# Principal_V01_R00.net
KiCad netlist of a schematic drawn in Altium Designer
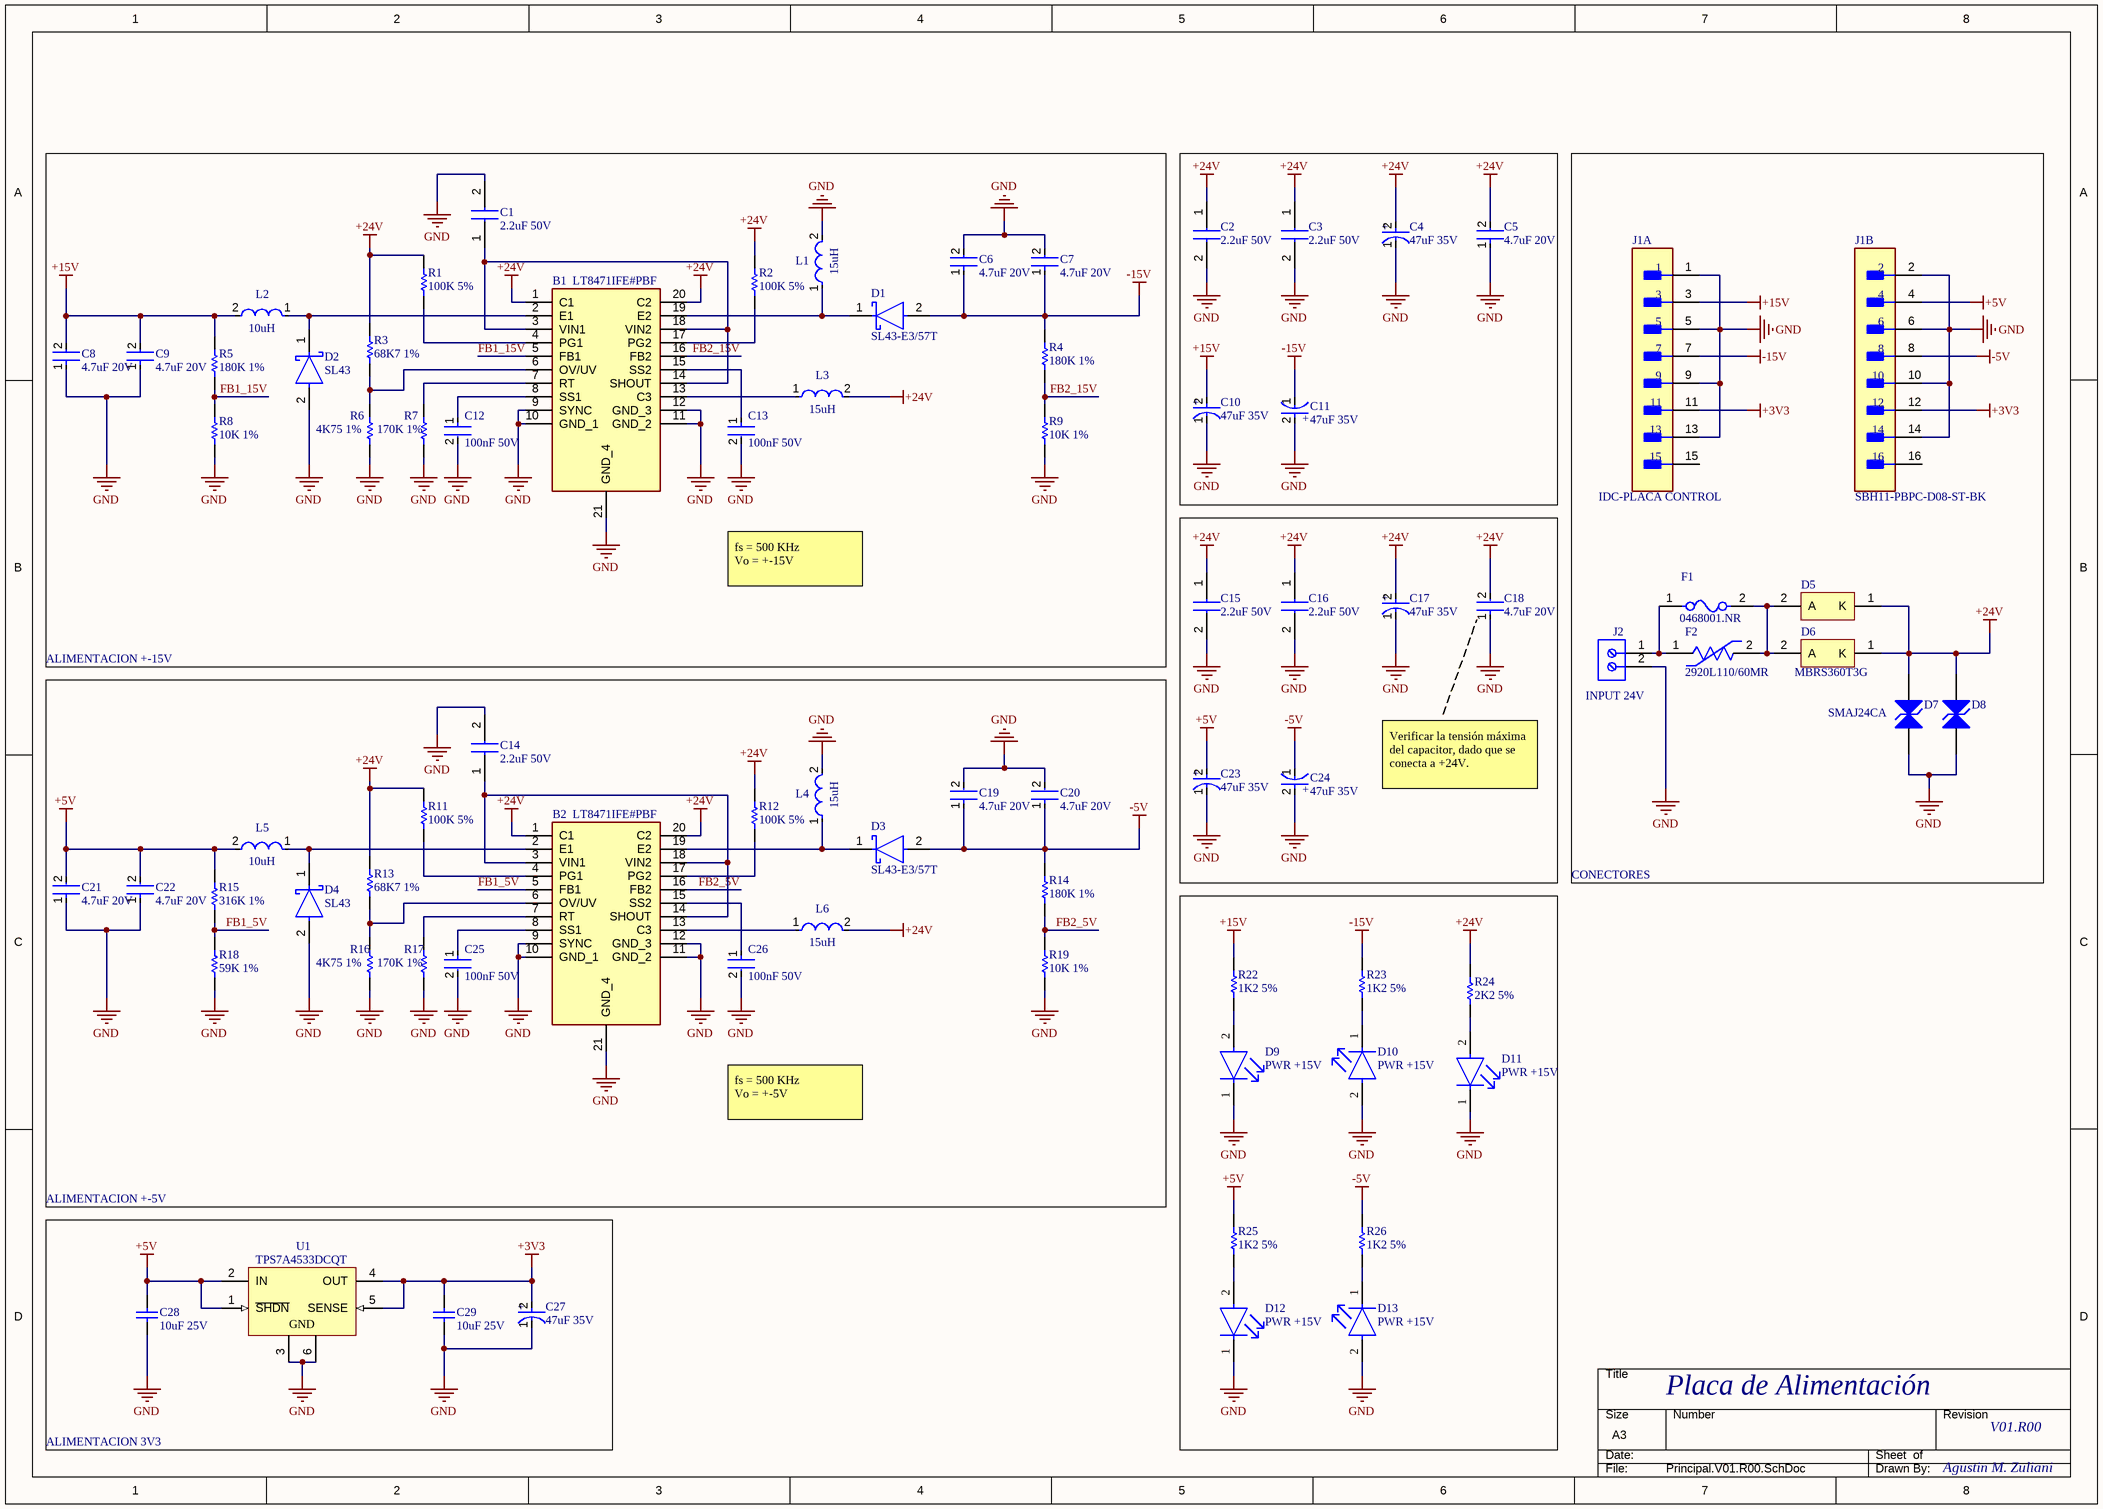
[diagram p0: Principal.V01.R00.SchDoc]

(export (version "E")
  (design (tool "Eeschema 10.0.6"))
  (components
    (comp (ref "B1")
      (value "LT8471IFE#PBF")
      (footprint "SOP65P640X120-21N")
      (fields (field (name "MOUSER PART NUMBER") "584-LT8471IFE#PBF"))
      (libsource (lib "LT8471IFE#PBF") (part "LT8471IFE#PBF"))
    )
    (comp (ref "B2")
      (value "LT8471IFE#PBF")
      (footprint "SOP65P640X120-21N")
      (fields (field (name "MOUSER PART NUMBER") "584-LT8471IFE#PBF"))
      (libsource (lib "LT8471IFE#PBF") (part "LT8471IFE#PBF"))
    )
    (comp (ref "C1")
      (value "2.2uF 50V")
      (footprint "SamacSys:MBASx31x")
      (description "Capacitor")
      (fields (field (name "MANUFACTURER_PART_NUMBER") "MBASU31LSB7225KTNA01"))
      (libsource (lib "SamacSys") (part "MBASU31LSB7225KTNA01"))
    )
    (comp (ref "C2")
      (value "2.2uF 50V")
      (footprint "SamacSys:MBASx31x")
      (description "Capacitor")
      (fields (field (name "MANUFACTURER_PART_NUMBER") "MBASU31LSB7225KTNA01"))
      (libsource (lib "SamacSys") (part "MBASU31LSB7225KTNA01"))
    )
    (comp (ref "C3")
      (value "2.2uF 50V")
      (footprint "SamacSys:MBASx31x")
      (description "Capacitor")
      (fields (field (name "MANUFACTURER_PART_NUMBER") "MBASU31LSB7225KTNA01"))
      (libsource (lib "SamacSys") (part "MBASU31LSB7225KTNA01"))
    )
    (comp (ref "C4")
      (value "47uF 35V")
      (footprint "FP-FK-D-MFG")
      (description "CAP ALUM 47UF 20% 35V SMD")
      (fields
        (field (name "MANUFACTURER") "Panasonic")
        (field (name "OCTOPART") "https://octopart.com/eeefk1v470p-panasonic-4642848")
      )
      (libsource (lib "Altium Content Vault") (part "a00bbbee19879c290e62620ae7e47b1"))
    )
    (comp (ref "C5")
      (value "4.7uF 20V")
      (footprint "FP-CC1206-1_25-MFG")
      (description "CAP CER 1UF 10V X7R 1206")
      (fields
        (field (name "MANUFACTURER") "Yageo")
        (field (name "OCTOPART") "https://octopart.com/cc1206kkx7r6bb105-yageo-21769912")
      )
      (libsource (lib "Altium Content Vault") (part "11868f565c42a9108669ba33697ecf6"))
    )
    (comp (ref "C6")
      (value "4.7uF 20V")
      (footprint "FP-CC1206-1_25-MFG")
      (description "CAP CER 1UF 10V X7R 1206")
      (fields
        (field (name "MANUFACTURER") "Yageo")
        (field (name "OCTOPART") "https://octopart.com/cc1206kkx7r6bb105-yageo-21769912")
      )
      (libsource (lib "Altium Content Vault") (part "11868f565c42a9108669ba33697ecf6"))
    )
    (comp (ref "C7")
      (value "4.7uF 20V")
      (footprint "FP-CC1206-1_25-MFG")
      (description "CAP CER 1UF 10V X7R 1206")
      (fields
        (field (name "MANUFACTURER") "Yageo")
        (field (name "OCTOPART") "https://octopart.com/cc1206kkx7r6bb105-yageo-21769912")
      )
      (libsource (lib "Altium Content Vault") (part "11868f565c42a9108669ba33697ecf6"))
    )
    (comp (ref "C8")
      (value "4.7uF 20V")
      (footprint "FP-CC1206-1_25-MFG")
      (description "CAP CER 1UF 10V X7R 1206")
      (fields
        (field (name "MANUFACTURER") "Yageo")
        (field (name "OCTOPART") "https://octopart.com/cc1206kkx7r6bb105-yageo-21769912")
      )
      (libsource (lib "Altium Content Vault") (part "11868f565c42a9108669ba33697ecf6"))
    )
    (comp (ref "C9")
      (value "4.7uF 20V")
      (footprint "FP-CC1206-1_25-MFG")
      (description "CAP CER 1UF 10V X7R 1206")
      (fields
        (field (name "MANUFACTURER") "Yageo")
        (field (name "OCTOPART") "https://octopart.com/cc1206kkx7r6bb105-yageo-21769912")
      )
      (libsource (lib "Altium Content Vault") (part "11868f565c42a9108669ba33697ecf6"))
    )
    (comp (ref "C10")
      (value "47uF 35V")
      (footprint "FP-FK-D-MFG")
      (description "CAP ALUM 47UF 20% 35V SMD")
      (fields
        (field (name "MANUFACTURER") "Panasonic")
        (field (name "OCTOPART") "https://octopart.com/eeefk1v470p-panasonic-4642848")
      )
      (libsource (lib "Altium Content Vault") (part "a00bbbee19879c290e62620ae7e47b1"))
    )
    (comp (ref "C11")
      (value "47uF 35V")
      (footprint "FP-FK-D-MFG")
      (description "CAP ALUM 47UF 20% 35V SMD")
      (fields
        (field (name "MANUFACTURER") "Panasonic")
        (field (name "OCTOPART") "https://octopart.com/eeefk1v470p-panasonic-4642848")
      )
      (libsource (lib "Altium Content Vault") (part "a00bbbee19879c290e62620ae7e47b1"))
    )
    (comp (ref "C12")
      (value "100nF 50V")
      (footprint "FP-C1206C-EB-MFG")
      (description "CAP CER 0.1UF 50V X7R 1206")
      (fields
        (field (name "MANUFACTURER") "KEMET")
        (field (name "OCTOPART") "https://octopart.com/c1206c104k5racauto-kemet-12595586")
      )
      (libsource (lib "Altium Content Vault") (part "b4654b650e69147ec39a6b967a45e02"))
    )
    (comp (ref "C13")
      (value "100nF 50V")
      (footprint "FP-C1206C-EB-MFG")
      (description "CAP CER 0.1UF 50V X7R 1206")
      (fields
        (field (name "MANUFACTURER") "KEMET")
        (field (name "OCTOPART") "https://octopart.com/c1206c104k5racauto-kemet-12595586")
      )
      (libsource (lib "Altium Content Vault") (part "b4654b650e69147ec39a6b967a45e02"))
    )
    (comp (ref "C14")
      (value "2.2uF 50V")
      (footprint "SamacSys:MBASx31x")
      (description "Capacitor")
      (fields (field (name "MANUFACTURER_PART_NUMBER") "MBASU31LSB7225KTNA01"))
      (libsource (lib "SamacSys") (part "MBASU31LSB7225KTNA01"))
    )
    (comp (ref "C15")
      (value "2.2uF 50V")
      (footprint "SamacSys:MBASx31x")
      (description "Capacitor")
      (fields (field (name "MANUFACTURER_PART_NUMBER") "MBASU31LSB7225KTNA01"))
      (libsource (lib "SamacSys") (part "MBASU31LSB7225KTNA01"))
    )
    (comp (ref "C16")
      (value "2.2uF 50V")
      (footprint "SamacSys:MBASx31x")
      (description "Capacitor")
      (fields (field (name "MANUFACTURER_PART_NUMBER") "MBASU31LSB7225KTNA01"))
      (libsource (lib "SamacSys") (part "MBASU31LSB7225KTNA01"))
    )
    (comp (ref "C17")
      (value "47uF 35V")
      (footprint "FP-FK-D-MFG")
      (description "CAP ALUM 47UF 20% 35V SMD")
      (fields
        (field (name "MANUFACTURER") "Panasonic")
        (field (name "OCTOPART") "https://octopart.com/eeefk1v470p-panasonic-4642848")
      )
      (libsource (lib "Altium Content Vault") (part "a00bbbee19879c290e62620ae7e47b1"))
    )
    (comp (ref "C18")
      (value "4.7uF 20V")
      (footprint "FP-CC1206-1_25-MFG")
      (description "CAP CER 1UF 10V X7R 1206")
      (fields
        (field (name "MANUFACTURER") "Yageo")
        (field (name "OCTOPART") "https://octopart.com/cc1206kkx7r6bb105-yageo-21769912")
      )
      (libsource (lib "Altium Content Vault") (part "11868f565c42a9108669ba33697ecf6"))
    )
    (comp (ref "C19")
      (value "4.7uF 20V")
      (footprint "FP-CC1206-1_25-MFG")
      (description "CAP CER 1UF 10V X7R 1206")
      (fields
        (field (name "MANUFACTURER") "Yageo")
        (field (name "OCTOPART") "https://octopart.com/cc1206kkx7r6bb105-yageo-21769912")
      )
      (libsource (lib "Altium Content Vault") (part "11868f565c42a9108669ba33697ecf6"))
    )
    (comp (ref "C20")
      (value "4.7uF 20V")
      (footprint "FP-CC1206-1_25-MFG")
      (description "CAP CER 1UF 10V X7R 1206")
      (fields
        (field (name "MANUFACTURER") "Yageo")
        (field (name "OCTOPART") "https://octopart.com/cc1206kkx7r6bb105-yageo-21769912")
      )
      (libsource (lib "Altium Content Vault") (part "11868f565c42a9108669ba33697ecf6"))
    )
    (comp (ref "C21")
      (value "4.7uF 20V")
      (footprint "FP-CC1206-1_25-MFG")
      (description "CAP CER 1UF 10V X7R 1206")
      (fields
        (field (name "MANUFACTURER") "Yageo")
        (field (name "OCTOPART") "https://octopart.com/cc1206kkx7r6bb105-yageo-21769912")
      )
      (libsource (lib "Altium Content Vault") (part "11868f565c42a9108669ba33697ecf6"))
    )
    (comp (ref "C22")
      (value "4.7uF 20V")
      (footprint "FP-CC1206-1_25-MFG")
      (description "CAP CER 1UF 10V X7R 1206")
      (fields
        (field (name "MANUFACTURER") "Yageo")
        (field (name "OCTOPART") "https://octopart.com/cc1206kkx7r6bb105-yageo-21769912")
      )
      (libsource (lib "Altium Content Vault") (part "11868f565c42a9108669ba33697ecf6"))
    )
    (comp (ref "C23")
      (value "47uF 35V")
      (footprint "FP-FK-D-MFG")
      (description "CAP ALUM 47UF 20% 35V SMD")
      (fields
        (field (name "MANUFACTURER") "Panasonic")
        (field (name "OCTOPART") "https://octopart.com/eeefk1v470p-panasonic-4642848")
      )
      (libsource (lib "Altium Content Vault") (part "a00bbbee19879c290e62620ae7e47b1"))
    )
    (comp (ref "C24")
      (value "47uF 35V")
      (footprint "FP-FK-D-MFG")
      (description "CAP ALUM 47UF 20% 35V SMD")
      (fields
        (field (name "MANUFACTURER") "Panasonic")
        (field (name "OCTOPART") "https://octopart.com/eeefk1v470p-panasonic-4642848")
      )
      (libsource (lib "Altium Content Vault") (part "a00bbbee19879c290e62620ae7e47b1"))
    )
    (comp (ref "C25")
      (value "100nF 50V")
      (footprint "FP-C1206C-EB-MFG")
      (description "CAP CER 0.1UF 50V X7R 1206")
      (fields
        (field (name "MANUFACTURER") "KEMET")
        (field (name "OCTOPART") "https://octopart.com/c1206c104k5racauto-kemet-12595586")
      )
      (libsource (lib "Altium Content Vault") (part "b4654b650e69147ec39a6b967a45e02"))
    )
    (comp (ref "C26")
      (value "100nF 50V")
      (footprint "FP-C1206C-EB-MFG")
      (description "CAP CER 0.1UF 50V X7R 1206")
      (fields
        (field (name "MANUFACTURER") "KEMET")
        (field (name "OCTOPART") "https://octopart.com/c1206c104k5racauto-kemet-12595586")
      )
      (libsource (lib "Altium Content Vault") (part "b4654b650e69147ec39a6b967a45e02"))
    )
    (comp (ref "C27")
      (value "47uF 35V")
      (footprint "FP-FK-D-MFG")
      (description "CAP ALUM 47UF 20% 35V SMD")
      (fields
        (field (name "MANUFACTURER") "Panasonic")
        (field (name "OCTOPART") "https://octopart.com/eeefk1v470p-panasonic-4642848")
      )
      (libsource (lib "Altium Content Vault") (part "a00bbbee19879c290e62620ae7e47b1"))
    )
    (comp (ref "C28")
      (value "10uF 25V")
      (footprint "CAPC1812(4532)280_L")
      (description "CAP 10uF 25V ±20% 1812 (4532 Metric) Thickness 2.8mm SMD")
      (fields (field (name "TOLERANCE") "Â±20%"))
      (libsource (lib "Altium Content Vault") (part "CAP"))
    )
    (comp (ref "C29")
      (value "10uF 25V")
      (footprint "CAPC1812(4532)280_L")
      (description "CAP 10uF 25V ±20% 1812 (4532 Metric) Thickness 2.8mm SMD")
      (fields (field (name "TOLERANCE") "Â±20%"))
      (libsource (lib "Altium Content Vault") (part "CAP"))
    )
    (comp (ref "D1")
      (value "SL43-E3/57T")
      (footprint "FP-95402-MFG")
      (description "DIODE SCHOTTKY 30V 4A DO214AB")
      (libsource (lib "Altium Content Vault") (part "1d6ec82d83fb6aee721767c19dac4b9"))
    )
    (comp (ref "D2")
      (value "SL43")
      (footprint "FP-95402-MFG")
      (description "DIODE SCHOTTKY 30V 4A DO214AB")
      (libsource (lib "Altium Content Vault") (part "1d6ec82d83fb6aee721767c19dac4b9"))
    )
    (comp (ref "D3")
      (value "SL43-E3/57T")
      (footprint "FP-95402-MFG")
      (description "DIODE SCHOTTKY 30V 4A DO214AB")
      (libsource (lib "Altium Content Vault") (part "1d6ec82d83fb6aee721767c19dac4b9"))
    )
    (comp (ref "D4")
      (value "SL43")
      (footprint "FP-95402-MFG")
      (description "DIODE SCHOTTKY 30V 4A DO214AB")
      (libsource (lib "Altium Content Vault") (part "1d6ec82d83fb6aee721767c19dac4b9"))
    )
    (comp (ref "D5")
      (value "MBRS360T3G")
      (footprint "ONSC-SMC-2-403-03_V")
      (description "Schottky Power Rectifier, 2-Pin SMC, Pb-Free, Tape and Reel")
      (fields (field (name "MANUFACTURER") "On Semiconductor"))
      (libsource (lib "Altium Content Vault") (part "ONSC-D-K1A2-2_A"))
    )
    (comp (ref "D6")
      (value "MBRS360T3G")
      (footprint "ONSC-SMC-2-403-03_V")
      (description "Schottky Power Rectifier, 2-Pin SMC, Pb-Free, Tape and Reel")
      (fields (field (name "MANUFACTURER") "On Semiconductor"))
      (libsource (lib "Altium Content Vault") (part "ONSC-D-K1A2-2_A"))
    )
    (comp (ref "D7")
      (value "SMAJ24CA")
      (footprint "VISH-DO-214AC-2_N")
      (fields
        (field (name "MANUFACTURER") "Vishay Semiconductor")
        (field (name "PARTNUMBER") "SMAJ24CA-E3/5A")
      )
      (libsource (lib "Altium Content Vault") (part "VISH-A1A2-2"))
    )
    (comp (ref "D8")
      (value "SMAJ24CA")
      (footprint "VISH-DO-214AC-2_N")
      (fields
        (field (name "MANUFACTURER") "Vishay Semiconductor")
        (field (name "PARTNUMBER") "SMAJ24CA-E3/5A")
      )
      (libsource (lib "Altium Content Vault") (part "VISH-A1A2-2"))
    )
    (comp (ref "D9")
      (value "PWR +15V")
      (footprint "FP-SML-LX0805UWC-TR-MFG")
      (description "SML-LX0805UWC-TR White LED, 0805 Diffused, Rectangle Lens SMD package")
      (libsource (lib "Altium Content Vault") (part "8706943c75ba83719d021d2fdc84c58"))
    )
    (comp (ref "D10")
      (value "PWR +15V")
      (footprint "FP-SML-LX0805UWC-TR-MFG")
      (description "SML-LX0805UWC-TR White LED, 0805 Diffused, Rectangle Lens SMD package")
      (libsource (lib "Altium Content Vault") (part "8706943c75ba83719d021d2fdc84c58"))
    )
    (comp (ref "D11")
      (value "PWR +15V")
      (footprint "FP-SML-LX0805UWC-TR-MFG")
      (description "SML-LX0805UWC-TR White LED, 0805 Diffused, Rectangle Lens SMD package")
      (libsource (lib "Altium Content Vault") (part "8706943c75ba83719d021d2fdc84c58"))
    )
    (comp (ref "D12")
      (value "PWR +15V")
      (footprint "FP-SML-LX0805UWC-TR-MFG")
      (description "SML-LX0805UWC-TR White LED, 0805 Diffused, Rectangle Lens SMD package")
      (libsource (lib "Altium Content Vault") (part "8706943c75ba83719d021d2fdc84c58"))
    )
    (comp (ref "D13")
      (value "PWR +15V")
      (footprint "FP-SML-LX0805UWC-TR-MFG")
      (description "SML-LX0805UWC-TR White LED, 0805 Diffused, Rectangle Lens SMD package")
      (libsource (lib "Altium Content Vault") (part "8706943c75ba83719d021d2fdc84c58"))
    )
    (comp (ref "F1")
      (value "0468001.NR")
      (footprint "FP-0468-MFG")
      (description "FUSE BOARD MNT 1A 63VAC/VDC 1206")
      (fields
        (field (name "MANUFACTURER") "Littelfuse")
        (field (name "OCTOPART") "https://octopart.com/0468001.nr-littelfuse-566477")
      )
      (libsource (lib "Altium Content Vault") (part "5bcf9b9f640e542cf0359d10258e979"))
    )
    (comp (ref "F2")
      (value "2920L110/60MR")
      (footprint "FP-2920L-MFG")
      (description "PTC RESET FUSE 60V 1.1A 2920")
      (fields
        (field (name "MANUFACTURER") "Littelfuse")
        (field (name "OCTOPART") "https://octopart.com/2920l110%2F60mr-littelfuse-75250824")
      )
      (libsource (lib "Altium Content Vault") (part "fc31388045fc42ab786d6d00b506e9f"))
    )
    (comp (ref "J1")
      (value "IDC-PLACA CONTROL")
      (footprint "FP-SBH11-PBPC-D08-ST-BK-MFG")
      (description "CONN HEADER VERT 16POS 2.54MM")
      (fields
        (field (name "OCTOPART") "https://octopart.com/sbh11-pbpc-d08-st-bk-sullins-12270491")
        (field (name "MANUFACTURER") "Sullins")
      )
      (libsource (lib "Altium Content Vault") (part "4b6d22b45e2f925f038cba5d936fbcc"))
    )
    (comp (ref "J2")
      (value "INPUT 24V")
      (footprint "691111710002")
      (description "111 Series 5MM Pitch Straight, Pcb Terminal Block, Through Hole, 2 Way")
      (libsource (lib "Altium Content Vault") (part "TBL - 1R - 02P - Screw"))
    )
    (comp (ref "L1")
      (value "15uH")
      (footprint "FP-NR6045-MFG")
      (description "Shielded Wirewound Inductor 15uH 20% 2.3A 91mΩ SMD")
      (fields (field (name "TOLERANCE") "20%"))
      (libsource (lib "") (part "725321dda6339637d4d059423bc1c3c_1"))
    )
    (comp (ref "L2")
      (value "10uH")
      (footprint "FP-NR10050-MFG")
      (description "Inductor Power Shielded Wirewound 10uH 20% 100KHz Ferrite 4.1A 32.5mΩ DCR T/R")
      (fields (field (name "TOLERANCE") "20%"))
      (libsource (lib "Altium Content Vault") (part "725321dda6339637d4d059423bc1c3c"))
    )
    (comp (ref "L3")
      (value "15uH")
      (footprint "FP-NR6045-MFG")
      (description "Shielded Wirewound Inductor 15uH 20% 2.3A 91mΩ SMD")
      (fields (field (name "TOLERANCE") "20%"))
      (libsource (lib "") (part "725321dda6339637d4d059423bc1c3c_1"))
    )
    (comp (ref "L4")
      (value "15uH")
      (footprint "FP-NR6045-MFG")
      (description "Shielded Wirewound Inductor 15uH 20% 2.3A 91mΩ SMD")
      (fields (field (name "TOLERANCE") "20%"))
      (libsource (lib "") (part "725321dda6339637d4d059423bc1c3c_1"))
    )
    (comp (ref "L5")
      (value "10uH")
      (footprint "FP-NR10050-MFG")
      (description "Inductor Power Shielded Wirewound 10uH 20% 100KHz Ferrite 4.1A 32.5mΩ DCR T/R")
      (fields (field (name "TOLERANCE") "20%"))
      (libsource (lib "Altium Content Vault") (part "725321dda6339637d4d059423bc1c3c"))
    )
    (comp (ref "L6")
      (value "15uH")
      (footprint "FP-NR6045-MFG")
      (description "Shielded Wirewound Inductor 15uH 20% 2.3A 91mΩ SMD")
      (fields (field (name "TOLERANCE") "20%"))
      (libsource (lib "") (part "725321dda6339637d4d059423bc1c3c_1"))
    )
    (comp (ref "R1")
      (value "100K 5%")
      (footprint "RESC0805(2012)_M")
      (description "124K 0.125W 1% 0805 (2012 Metric)  SMD")
      (fields (field (name "POWER") "0.125 W") (field (name "TOLERANCE") "1 %"))
      (libsource (lib "Altium Content Vault") (part "RES"))
    )
    (comp (ref "R2")
      (value "100K 5%")
      (footprint "RESC0805(2012)_M")
      (description "124K 0.125W 1% 0805 (2012 Metric)  SMD")
      (fields (field (name "POWER") "0.125 W") (field (name "TOLERANCE") "1 %"))
      (libsource (lib "Altium Content Vault") (part "RES"))
    )
    (comp (ref "R3")
      (value "68K7 1%")
      (footprint "RESC0805(2012)_M")
      (description "124K 0.125W 1% 0805 (2012 Metric)  SMD")
      (fields (field (name "POWER") "0.125 W") (field (name "TOLERANCE") "1 %"))
      (libsource (lib "Altium Content Vault") (part "RES"))
    )
    (comp (ref "R4")
      (value "180K 1%")
      (footprint "RESC0805(2012)_M")
      (description "124K 0.125W 1% 0805 (2012 Metric)  SMD")
      (fields (field (name "POWER") "0.125 W") (field (name "TOLERANCE") "1 %"))
      (libsource (lib "Altium Content Vault") (part "RES"))
    )
    (comp (ref "R5")
      (value "180K 1%")
      (footprint "RESC0805(2012)_M")
      (description "124K 0.125W 1% 0805 (2012 Metric)  SMD")
      (fields (field (name "POWER") "0.125 W") (field (name "TOLERANCE") "1 %"))
      (libsource (lib "Altium Content Vault") (part "RES"))
    )
    (comp (ref "R6")
      (value "4K75 1%")
      (footprint "RESC0805(2012)_M")
      (description "124K 0.125W 1% 0805 (2012 Metric)  SMD")
      (fields (field (name "POWER") "0.125 W") (field (name "TOLERANCE") "1 %"))
      (libsource (lib "Altium Content Vault") (part "RES"))
    )
    (comp (ref "R7")
      (value "170K 1%")
      (footprint "RESC0805(2012)_M")
      (description "124K 0.125W 1% 0805 (2012 Metric)  SMD")
      (fields (field (name "POWER") "0.125 W") (field (name "TOLERANCE") "1 %"))
      (libsource (lib "Altium Content Vault") (part "RES"))
    )
    (comp (ref "R8")
      (value "10K 1%")
      (footprint "RESC0805(2012)_M")
      (description "124K 0.125W 1% 0805 (2012 Metric)  SMD")
      (fields (field (name "POWER") "0.125 W") (field (name "TOLERANCE") "1 %"))
      (libsource (lib "Altium Content Vault") (part "RES"))
    )
    (comp (ref "R9")
      (value "10K 1%")
      (footprint "RESC0805(2012)_M")
      (description "124K 0.125W 1% 0805 (2012 Metric)  SMD")
      (fields (field (name "POWER") "0.125 W") (field (name "TOLERANCE") "1 %"))
      (libsource (lib "Altium Content Vault") (part "RES"))
    )
    (comp (ref "R11")
      (value "100K 5%")
      (footprint "RESC0805(2012)_M")
      (description "124K 0.125W 1% 0805 (2012 Metric)  SMD")
      (fields (field (name "POWER") "0.125 W") (field (name "TOLERANCE") "1 %"))
      (libsource (lib "Altium Content Vault") (part "RES"))
    )
    (comp (ref "R12")
      (value "100K 5%")
      (footprint "RESC0805(2012)_M")
      (description "124K 0.125W 1% 0805 (2012 Metric)  SMD")
      (fields (field (name "POWER") "0.125 W") (field (name "TOLERANCE") "1 %"))
      (libsource (lib "Altium Content Vault") (part "RES"))
    )
    (comp (ref "R13")
      (value "68K7 1%")
      (footprint "RESC0805(2012)_M")
      (description "124K 0.125W 1% 0805 (2012 Metric)  SMD")
      (fields (field (name "POWER") "0.125 W") (field (name "TOLERANCE") "1 %"))
      (libsource (lib "Altium Content Vault") (part "RES"))
    )
    (comp (ref "R14")
      (value "180K 1%")
      (footprint "RESC0805(2012)_M")
      (description "124K 0.125W 1% 0805 (2012 Metric)  SMD")
      (fields (field (name "POWER") "0.125 W") (field (name "TOLERANCE") "1 %"))
      (libsource (lib "Altium Content Vault") (part "RES"))
    )
    (comp (ref "R15")
      (value "316K 1%")
      (footprint "RESC0805(2012)_M")
      (description "124K 0.125W 1% 0805 (2012 Metric)  SMD")
      (fields (field (name "POWER") "0.125 W") (field (name "TOLERANCE") "1 %"))
      (libsource (lib "Altium Content Vault") (part "RES"))
    )
    (comp (ref "R16")
      (value "4K75 1%")
      (footprint "RESC0805(2012)_M")
      (description "124K 0.125W 1% 0805 (2012 Metric)  SMD")
      (fields (field (name "POWER") "0.125 W") (field (name "TOLERANCE") "1 %"))
      (libsource (lib "Altium Content Vault") (part "RES"))
    )
    (comp (ref "R17")
      (value "170K 1%")
      (footprint "RESC0805(2012)_M")
      (description "124K 0.125W 1% 0805 (2012 Metric)  SMD")
      (fields (field (name "POWER") "0.125 W") (field (name "TOLERANCE") "1 %"))
      (libsource (lib "Altium Content Vault") (part "RES"))
    )
    (comp (ref "R18")
      (value "59K 1%")
      (footprint "RESC0805(2012)_M")
      (description "124K 0.125W 1% 0805 (2012 Metric)  SMD")
      (fields (field (name "POWER") "0.125 W") (field (name "TOLERANCE") "1 %"))
      (libsource (lib "Altium Content Vault") (part "RES"))
    )
    (comp (ref "R19")
      (value "10K 1%")
      (footprint "RESC0805(2012)_M")
      (description "124K 0.125W 1% 0805 (2012 Metric)  SMD")
      (fields (field (name "POWER") "0.125 W") (field (name "TOLERANCE") "1 %"))
      (libsource (lib "Altium Content Vault") (part "RES"))
    )
    (comp (ref "R22")
      (value "1K2 5%")
      (footprint "RESC0805(2012)_M")
      (description "124K 0.125W 1% 0805 (2012 Metric)  SMD")
      (fields (field (name "POWER") "0.125 W") (field (name "TOLERANCE") "1 %"))
      (libsource (lib "Altium Content Vault") (part "RES"))
    )
    (comp (ref "R23")
      (value "1K2 5%")
      (footprint "RESC0805(2012)_M")
      (description "124K 0.125W 1% 0805 (2012 Metric)  SMD")
      (fields (field (name "POWER") "0.125 W") (field (name "TOLERANCE") "1 %"))
      (libsource (lib "Altium Content Vault") (part "RES"))
    )
    (comp (ref "R24")
      (value "2K2 5%")
      (footprint "RESC0805(2012)_M")
      (description "124K 0.125W 1% 0805 (2012 Metric)  SMD")
      (fields (field (name "POWER") "0.125 W") (field (name "TOLERANCE") "1 %"))
      (libsource (lib "Altium Content Vault") (part "RES"))
    )
    (comp (ref "R25")
      (value "1K2 5%")
      (footprint "RESC0805(2012)_M")
      (description "124K 0.125W 1% 0805 (2012 Metric)  SMD")
      (fields (field (name "POWER") "0.125 W") (field (name "TOLERANCE") "1 %"))
      (libsource (lib "Altium Content Vault") (part "RES"))
    )
    (comp (ref "R26")
      (value "1K2 5%")
      (footprint "RESC0805(2012)_M")
      (description "124K 0.125W 1% 0805 (2012 Metric)  SMD")
      (fields (field (name "POWER") "0.125 W") (field (name "TOLERANCE") "1 %"))
      (libsource (lib "Altium Content Vault") (part "RES"))
    )
    (comp (ref "U1")
      (value "TPS7A4533DCQT")
      (footprint "DCQ0006A_M")
      (fields (field (name "MANUFACTURER") "Texas Instruments"))
      (libsource (lib "Altium Content Vault") (part "TI-TXXXXAXXXDCQ_KTTX"))
    )
  )
  (nets
    (net (code "1") (name "+3V3") (class "Default")
      (node (ref "C27") (pin "2") (pinfunction "A_2") (pintype "passive"))
      (node (ref "C29") (pin "2") (pinfunction "2_2") (pintype "passive"))
      (node (ref "J1") (pin "11") (pinfunction "11_11") (pintype "passive"))
      (node (ref "J1") (pin "12") (pinfunction "12_12") (pintype "passive"))
      (node (ref "U1") (pin "4") (pinfunction "OUT_4") (pintype "power_in"))
      (node (ref "U1") (pin "5") (pinfunction "SENSE_5") (pintype "input"))
    )
    (net (code "2") (name "+5V") (class "Default")
      (node (ref "C21") (pin "2") (pinfunction "2_2") (pintype "passive"))
      (node (ref "C22") (pin "2") (pinfunction "2_2") (pintype "passive"))
      (node (ref "C23") (pin "2") (pinfunction "A_2") (pintype "passive"))
      (node (ref "C28") (pin "2") (pinfunction "2_2") (pintype "passive"))
      (node (ref "J1") (pin "4") (pinfunction "4_4") (pintype "passive"))
      (node (ref "L5") (pin "2") (pinfunction "2_2") (pintype "passive"))
      (node (ref "R15") (pin "2") (pinfunction "2_2") (pintype "passive"))
      (node (ref "R25") (pin "1") (pinfunction "1_1") (pintype "passive"))
      (node (ref "U1") (pin "1") (pinfunction "~{SHDN}_1") (pintype "input"))
      (node (ref "U1") (pin "2") (pinfunction "IN_2") (pintype "power_in"))
    )
    (net (code "3") (name "+15V") (class "Default")
      (node (ref "C10") (pin "2") (pinfunction "A_2") (pintype "passive"))
      (node (ref "C8") (pin "2") (pinfunction "2_2") (pintype "passive"))
      (node (ref "C9") (pin "2") (pinfunction "2_2") (pintype "passive"))
      (node (ref "J1") (pin "3") (pinfunction "3_3") (pintype "passive"))
      (node (ref "L2") (pin "2") (pinfunction "2_2") (pintype "passive"))
      (node (ref "R22") (pin "1") (pinfunction "1_1") (pintype "passive"))
      (node (ref "R5") (pin "2") (pinfunction "2_2") (pintype "passive"))
    )
    (net (code "4") (name "+24V") (class "Default")
      (node (ref "B1") (pin "1") (pinfunction "C1_1") (pintype "passive"))
      (node (ref "B1") (pin "20") (pinfunction "C2_20") (pintype "passive"))
      (node (ref "B2") (pin "1") (pinfunction "C1_1") (pintype "passive"))
      (node (ref "B2") (pin "20") (pinfunction "C2_20") (pintype "passive"))
      (node (ref "C15") (pin "1") (pinfunction "1_1") (pintype "passive"))
      (node (ref "C16") (pin "1") (pinfunction "1_1") (pintype "passive"))
      (node (ref "C17") (pin "2") (pinfunction "A_2") (pintype "passive"))
      (node (ref "C18") (pin "2") (pinfunction "2_2") (pintype "passive"))
      (node (ref "C2") (pin "1") (pinfunction "1_1") (pintype "passive"))
      (node (ref "C3") (pin "1") (pinfunction "1_1") (pintype "passive"))
      (node (ref "C4") (pin "2") (pinfunction "A_2") (pintype "passive"))
      (node (ref "C5") (pin "2") (pinfunction "2_2") (pintype "passive"))
      (node (ref "D5") (pin "1") (pinfunction "K_1") (pintype "passive"))
      (node (ref "D6") (pin "1") (pinfunction "K_1") (pintype "passive"))
      (node (ref "D7") (pin "2") (pinfunction "A2_2") (pintype "passive"))
      (node (ref "D8") (pin "2") (pinfunction "A2_2") (pintype "passive"))
      (node (ref "L3") (pin "2") (pinfunction "2_2") (pintype "passive"))
      (node (ref "L6") (pin "2") (pinfunction "2_2") (pintype "passive"))
      (node (ref "R1") (pin "2") (pinfunction "2_2") (pintype "passive"))
      (node (ref "R11") (pin "2") (pinfunction "2_2") (pintype "passive"))
      (node (ref "R12") (pin "1") (pinfunction "1_1") (pintype "passive"))
      (node (ref "R13") (pin "2") (pinfunction "2_2") (pintype "passive"))
      (node (ref "R2") (pin "1") (pinfunction "1_1") (pintype "passive"))
      (node (ref "R24") (pin "1") (pinfunction "1_1") (pintype "passive"))
      (node (ref "R3") (pin "2") (pinfunction "2_2") (pintype "passive"))
    )
    (net (code "5") (name "-5V") (class "Default")
      (node (ref "C19") (pin "1") (pinfunction "1_1") (pintype "passive"))
      (node (ref "C20") (pin "1") (pinfunction "1_1") (pintype "passive"))
      (node (ref "C24") (pin "1") (pinfunction "C_1") (pintype "passive"))
      (node (ref "D3") (pin "2") (pinfunction "A_2") (pintype "passive"))
      (node (ref "J1") (pin "8") (pinfunction "8_8") (pintype "passive"))
      (node (ref "R14") (pin "2") (pinfunction "2_2") (pintype "passive"))
      (node (ref "R26") (pin "1") (pinfunction "1_1") (pintype "passive"))
    )
    (net (code "6") (name "-15V") (class "Default")
      (node (ref "C11") (pin "1") (pinfunction "C_1") (pintype "passive"))
      (node (ref "C6") (pin "1") (pinfunction "1_1") (pintype "passive"))
      (node (ref "C7") (pin "1") (pinfunction "1_1") (pintype "passive"))
      (node (ref "D1") (pin "2") (pinfunction "A_2") (pintype "passive"))
      (node (ref "J1") (pin "7") (pinfunction "7_7") (pintype "passive"))
      (node (ref "R23") (pin "1") (pinfunction "1_1") (pintype "passive"))
      (node (ref "R4") (pin "2") (pinfunction "2_2") (pintype "passive"))
    )
    (net (code "7") (name "/FB1_5V") (class "Default")
      (node (ref "B2") (pin "5") (pinfunction "FB1_5") (pintype "passive"))
      (node (ref "R15") (pin "1") (pinfunction "1_1") (pintype "passive"))
      (node (ref "R18") (pin "2") (pinfunction "2_2") (pintype "passive"))
    )
    (net (code "8") (name "/FB1_15V") (class "Default")
      (node (ref "B1") (pin "5") (pinfunction "FB1_5") (pintype "passive"))
      (node (ref "R5") (pin "1") (pinfunction "1_1") (pintype "passive"))
      (node (ref "R8") (pin "2") (pinfunction "2_2") (pintype "passive"))
    )
    (net (code "9") (name "/FB2_5V") (class "Default")
      (node (ref "B2") (pin "16") (pinfunction "FB2_16") (pintype "passive"))
      (node (ref "R14") (pin "1") (pinfunction "1_1") (pintype "passive"))
      (node (ref "R19") (pin "2") (pinfunction "2_2") (pintype "passive"))
    )
    (net (code "10") (name "/FB2_15V") (class "Default")
      (node (ref "B1") (pin "16") (pinfunction "FB2_16") (pintype "passive"))
      (node (ref "R4") (pin "1") (pinfunction "1_1") (pintype "passive"))
      (node (ref "R9") (pin "2") (pinfunction "2_2") (pintype "passive"))
    )
    (net (code "11") (name "GND") (class "Default")
      (node (ref "B1") (pin "10") (pinfunction "GND_1_10") (pintype "passive"))
      (node (ref "B1") (pin "11") (pinfunction "GND_2_11") (pintype "passive"))
      (node (ref "B1") (pin "12") (pinfunction "GND_3_12") (pintype "passive"))
      (node (ref "B1") (pin "21") (pinfunction "GND_4_21") (pintype "passive"))
      (node (ref "B1") (pin "9") (pinfunction "SYNC_9") (pintype "passive"))
      (node (ref "B2") (pin "10") (pinfunction "GND_1_10") (pintype "passive"))
      (node (ref "B2") (pin "11") (pinfunction "GND_2_11") (pintype "passive"))
      (node (ref "B2") (pin "12") (pinfunction "GND_3_12") (pintype "passive"))
      (node (ref "B2") (pin "21") (pinfunction "GND_4_21") (pintype "passive"))
      (node (ref "B2") (pin "9") (pinfunction "SYNC_9") (pintype "passive"))
      (node (ref "C1") (pin "2") (pinfunction "2_2") (pintype "passive"))
      (node (ref "C10") (pin "1") (pinfunction "C_1") (pintype "passive"))
      (node (ref "C11") (pin "2") (pinfunction "A_2") (pintype "passive"))
      (node (ref "C12") (pin "2") (pinfunction "2_2") (pintype "passive"))
      (node (ref "C13") (pin "2") (pinfunction "2_2") (pintype "passive"))
      (node (ref "C14") (pin "2") (pinfunction "2_2") (pintype "passive"))
      (node (ref "C15") (pin "2") (pinfunction "2_2") (pintype "passive"))
      (node (ref "C16") (pin "2") (pinfunction "2_2") (pintype "passive"))
      (node (ref "C17") (pin "1") (pinfunction "C_1") (pintype "passive"))
      (node (ref "C18") (pin "1") (pinfunction "1_1") (pintype "passive"))
      (node (ref "C19") (pin "2") (pinfunction "2_2") (pintype "passive"))
      (node (ref "C2") (pin "2") (pinfunction "2_2") (pintype "passive"))
      (node (ref "C20") (pin "2") (pinfunction "2_2") (pintype "passive"))
      (node (ref "C21") (pin "1") (pinfunction "1_1") (pintype "passive"))
      (node (ref "C22") (pin "1") (pinfunction "1_1") (pintype "passive"))
      (node (ref "C23") (pin "1") (pinfunction "C_1") (pintype "passive"))
      (node (ref "C24") (pin "2") (pinfunction "A_2") (pintype "passive"))
      (node (ref "C25") (pin "2") (pinfunction "2_2") (pintype "passive"))
      (node (ref "C26") (pin "2") (pinfunction "2_2") (pintype "passive"))
      (node (ref "C27") (pin "1") (pinfunction "C_1") (pintype "passive"))
      (node (ref "C28") (pin "1") (pinfunction "1_1") (pintype "passive"))
      (node (ref "C29") (pin "1") (pinfunction "1_1") (pintype "passive"))
      (node (ref "C3") (pin "2") (pinfunction "2_2") (pintype "passive"))
      (node (ref "C4") (pin "1") (pinfunction "C_1") (pintype "passive"))
      (node (ref "C5") (pin "1") (pinfunction "1_1") (pintype "passive"))
      (node (ref "C6") (pin "2") (pinfunction "2_2") (pintype "passive"))
      (node (ref "C7") (pin "2") (pinfunction "2_2") (pintype "passive"))
      (node (ref "C8") (pin "1") (pinfunction "1_1") (pintype "passive"))
      (node (ref "C9") (pin "1") (pinfunction "1_1") (pintype "passive"))
      (node (ref "D10") (pin "2") (pinfunction "A_2") (pintype "passive"))
      (node (ref "D11") (pin "1") (pinfunction "C_1") (pintype "passive"))
      (node (ref "D12") (pin "1") (pinfunction "C_1") (pintype "passive"))
      (node (ref "D13") (pin "2") (pinfunction "A_2") (pintype "passive"))
      (node (ref "D2") (pin "2") (pinfunction "A_2") (pintype "passive"))
      (node (ref "D4") (pin "2") (pinfunction "A_2") (pintype "passive"))
      (node (ref "D7") (pin "1") (pinfunction "A1_1") (pintype "passive"))
      (node (ref "D8") (pin "1") (pinfunction "A1_1") (pintype "passive"))
      (node (ref "D9") (pin "1") (pinfunction "C_1") (pintype "passive"))
      (node (ref "J1") (pin "1") (pinfunction "1_1") (pintype "passive"))
      (node (ref "J1") (pin "10") (pinfunction "10_10") (pintype "passive"))
      (node (ref "J1") (pin "13") (pinfunction "13_13") (pintype "passive"))
      (node (ref "J1") (pin "14") (pinfunction "14_14") (pintype "passive"))
      (node (ref "J1") (pin "2") (pinfunction "2_2") (pintype "passive"))
      (node (ref "J1") (pin "5") (pinfunction "5_5") (pintype "passive"))
      (node (ref "J1") (pin "6") (pinfunction "6_6") (pintype "passive"))
      (node (ref "J1") (pin "9") (pinfunction "9_9") (pintype "passive"))
      (node (ref "J2") (pin "2") (pinfunction "2_2") (pintype "passive"))
      (node (ref "L1") (pin "2") (pinfunction "2_2") (pintype "passive"))
      (node (ref "L4") (pin "2") (pinfunction "2_2") (pintype "passive"))
      (node (ref "R16") (pin "1") (pinfunction "1_1") (pintype "passive"))
      (node (ref "R17") (pin "1") (pinfunction "1_1") (pintype "passive"))
      (node (ref "R18") (pin "1") (pinfunction "1_1") (pintype "passive"))
      (node (ref "R19") (pin "1") (pinfunction "1_1") (pintype "passive"))
      (node (ref "R6") (pin "1") (pinfunction "1_1") (pintype "passive"))
      (node (ref "R7") (pin "1") (pinfunction "1_1") (pintype "passive"))
      (node (ref "R8") (pin "1") (pinfunction "1_1") (pintype "passive"))
      (node (ref "R9") (pin "1") (pinfunction "1_1") (pintype "passive"))
      (node (ref "U1") (pin "3") (pinfunction "GND_3") (pintype "power_in"))
      (node (ref "U1") (pin "6") (pinfunction "GND_6") (pintype "power_in"))
    )
    (net (code "12") (name "Net-(B1-C3)") (class "Default")
      (node (ref "B1") (pin "13") (pinfunction "C3_13") (pintype "passive"))
      (node (ref "L3") (pin "1") (pinfunction "1_1") (pintype "passive"))
    )
    (net (code "13") (name "Net-(B1-E1)") (class "Default")
      (node (ref "B1") (pin "2") (pinfunction "E1_2") (pintype "passive"))
      (node (ref "D2") (pin "1") (pinfunction "C_1") (pintype "passive"))
      (node (ref "L2") (pin "1") (pinfunction "1_1") (pintype "passive"))
    )
    (net (code "14") (name "Net-(B1-E2)") (class "Default")
      (node (ref "B1") (pin "19") (pinfunction "E2_19") (pintype "passive"))
      (node (ref "D1") (pin "1") (pinfunction "C_1") (pintype "passive"))
      (node (ref "L1") (pin "1") (pinfunction "1_1") (pintype "passive"))
    )
    (net (code "15") (name "Net-(B1-OV{slash}UV)") (class "Default")
      (node (ref "B1") (pin "6") (pinfunction "OV/UV_6") (pintype "passive"))
      (node (ref "R3") (pin "1") (pinfunction "1_1") (pintype "passive"))
      (node (ref "R6") (pin "2") (pinfunction "2_2") (pintype "passive"))
    )
    (net (code "16") (name "Net-(B1-PG1)") (class "Default")
      (node (ref "B1") (pin "4") (pinfunction "PG1_4") (pintype "passive"))
      (node (ref "R1") (pin "1") (pinfunction "1_1") (pintype "passive"))
    )
    (net (code "17") (name "Net-(B1-PG2)") (class "Default")
      (node (ref "B1") (pin "17") (pinfunction "PG2_17") (pintype "passive"))
      (node (ref "R2") (pin "2") (pinfunction "2_2") (pintype "passive"))
    )
    (net (code "18") (name "Net-(B1-RT)") (class "Default")
      (node (ref "B1") (pin "7") (pinfunction "RT_7") (pintype "passive"))
      (node (ref "R7") (pin "2") (pinfunction "2_2") (pintype "passive"))
    )
    (net (code "19") (name "Net-(B1-SHOUT)") (class "Default")
      (node (ref "B1") (pin "14") (pinfunction "SHOUT_14") (pintype "passive"))
      (node (ref "B1") (pin "18") (pinfunction "VIN2_18") (pintype "passive"))
      (node (ref "B1") (pin "3") (pinfunction "VIN1_3") (pintype "passive"))
      (node (ref "C1") (pin "1") (pinfunction "1_1") (pintype "passive"))
    )
    (net (code "20") (name "Net-(B1-SS1)") (class "Default")
      (node (ref "B1") (pin "8") (pinfunction "SS1_8") (pintype "passive"))
      (node (ref "C12") (pin "1") (pinfunction "1_1") (pintype "passive"))
    )
    (net (code "21") (name "Net-(B1-SS2)") (class "Default")
      (node (ref "B1") (pin "15") (pinfunction "SS2_15") (pintype "passive"))
      (node (ref "C13") (pin "1") (pinfunction "1_1") (pintype "passive"))
    )
    (net (code "22") (name "Net-(B2-C3)") (class "Default")
      (node (ref "B2") (pin "13") (pinfunction "C3_13") (pintype "passive"))
      (node (ref "L6") (pin "1") (pinfunction "1_1") (pintype "passive"))
    )
    (net (code "23") (name "Net-(B2-E1)") (class "Default")
      (node (ref "B2") (pin "2") (pinfunction "E1_2") (pintype "passive"))
      (node (ref "D4") (pin "1") (pinfunction "C_1") (pintype "passive"))
      (node (ref "L5") (pin "1") (pinfunction "1_1") (pintype "passive"))
    )
    (net (code "24") (name "Net-(B2-E2)") (class "Default")
      (node (ref "B2") (pin "19") (pinfunction "E2_19") (pintype "passive"))
      (node (ref "D3") (pin "1") (pinfunction "C_1") (pintype "passive"))
      (node (ref "L4") (pin "1") (pinfunction "1_1") (pintype "passive"))
    )
    (net (code "25") (name "Net-(B2-OV{slash}UV)") (class "Default")
      (node (ref "B2") (pin "6") (pinfunction "OV/UV_6") (pintype "passive"))
      (node (ref "R13") (pin "1") (pinfunction "1_1") (pintype "passive"))
      (node (ref "R16") (pin "2") (pinfunction "2_2") (pintype "passive"))
    )
    (net (code "26") (name "Net-(B2-PG1)") (class "Default")
      (node (ref "B2") (pin "4") (pinfunction "PG1_4") (pintype "passive"))
      (node (ref "R11") (pin "1") (pinfunction "1_1") (pintype "passive"))
    )
    (net (code "27") (name "Net-(B2-PG2)") (class "Default")
      (node (ref "B2") (pin "17") (pinfunction "PG2_17") (pintype "passive"))
      (node (ref "R12") (pin "2") (pinfunction "2_2") (pintype "passive"))
    )
    (net (code "28") (name "Net-(B2-RT)") (class "Default")
      (node (ref "B2") (pin "7") (pinfunction "RT_7") (pintype "passive"))
      (node (ref "R17") (pin "2") (pinfunction "2_2") (pintype "passive"))
    )
    (net (code "29") (name "Net-(B2-SHOUT)") (class "Default")
      (node (ref "B2") (pin "14") (pinfunction "SHOUT_14") (pintype "passive"))
      (node (ref "B2") (pin "18") (pinfunction "VIN2_18") (pintype "passive"))
      (node (ref "B2") (pin "3") (pinfunction "VIN1_3") (pintype "passive"))
      (node (ref "C14") (pin "1") (pinfunction "1_1") (pintype "passive"))
    )
    (net (code "30") (name "Net-(B2-SS1)") (class "Default")
      (node (ref "B2") (pin "8") (pinfunction "SS1_8") (pintype "passive"))
      (node (ref "C25") (pin "1") (pinfunction "1_1") (pintype "passive"))
    )
    (net (code "31") (name "Net-(B2-SS2)") (class "Default")
      (node (ref "B2") (pin "15") (pinfunction "SS2_15") (pintype "passive"))
      (node (ref "C26") (pin "1") (pinfunction "1_1") (pintype "passive"))
    )
    (net (code "32") (name "Net-(D5-A)") (class "Default")
      (node (ref "D5") (pin "2") (pinfunction "A_2") (pintype "passive"))
      (node (ref "D6") (pin "2") (pinfunction "A_2") (pintype "passive"))
      (node (ref "F1") (pin "2") (pinfunction "2_2") (pintype "passive"))
      (node (ref "F2") (pin "2") (pinfunction "2_2") (pintype "passive"))
    )
    (net (code "33") (name "Net-(D9-A)") (class "Default")
      (node (ref "D9") (pin "2") (pinfunction "A_2") (pintype "passive"))
      (node (ref "R22") (pin "2") (pinfunction "2_2") (pintype "passive"))
    )
    (net (code "34") (name "Net-(D10-C)") (class "Default")
      (node (ref "D10") (pin "1") (pinfunction "C_1") (pintype "passive"))
      (node (ref "R23") (pin "2") (pinfunction "2_2") (pintype "passive"))
    )
    (net (code "35") (name "Net-(D11-A)") (class "Default")
      (node (ref "D11") (pin "2") (pinfunction "A_2") (pintype "passive"))
      (node (ref "R24") (pin "2") (pinfunction "2_2") (pintype "passive"))
    )
    (net (code "36") (name "Net-(D12-A)") (class "Default")
      (node (ref "D12") (pin "2") (pinfunction "A_2") (pintype "passive"))
      (node (ref "R25") (pin "2") (pinfunction "2_2") (pintype "passive"))
    )
    (net (code "37") (name "Net-(D13-C)") (class "Default")
      (node (ref "D13") (pin "1") (pinfunction "C_1") (pintype "passive"))
      (node (ref "R26") (pin "2") (pinfunction "2_2") (pintype "passive"))
    )
    (net (code "38") (name "Net-(F1-Pad1)") (class "Default")
      (node (ref "F1") (pin "1") (pinfunction "1_1") (pintype "passive"))
      (node (ref "F2") (pin "1") (pinfunction "1_1") (pintype "passive"))
      (node (ref "J2") (pin "1") (pinfunction "1_1") (pintype "passive"))
    )
    (net (code "39") (name "unconnected-(J1-Pad15)") (class "Default")
      (node (ref "J1") (pin "15") (pinfunction "15_15") (pintype "passive"))
    )
    (net (code "40") (name "unconnected-(J1-Pad16)") (class "Default")
      (node (ref "J1") (pin "16") (pinfunction "16_16") (pintype "passive"))
    )
  )
)
